# KEY.net
KiCad netlist of a schematic drawn in Altium Designer
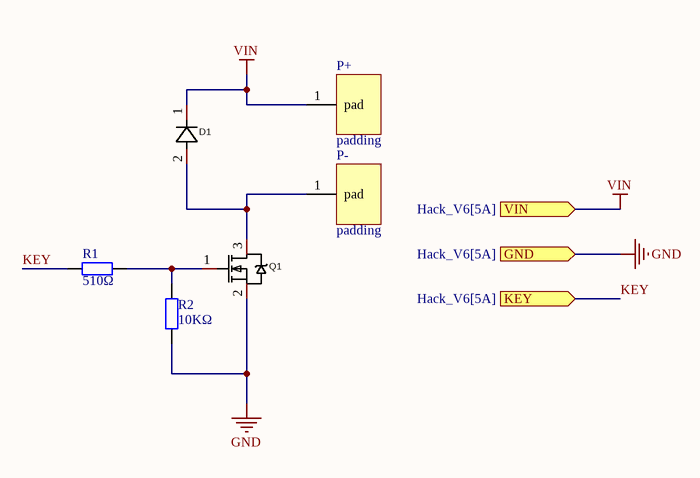
[diagram p0: KEY.SchDoc]

(export (version "E")
  (design (tool "Eeschema 10.0.6"))
  (components
    (comp (ref "D1")
      (value "DSK16")
      (footprint "DSK16")
      (fields (field (name "MANUFACTURER") "HXY MOSFET(华轩阳电子)"))
      (libsource (lib "Hack_V4") (part "DSK16"))
    )
    (comp (ref "P+") (value "padding") (footprint "PADDING1") (libsource (lib "Hack_V4") (part "padding1")))
    (comp (ref "P-") (value "padding") (footprint "PADDING1") (libsource (lib "Hack_V4") (part "padding1")))
    (comp (ref "Q1")
      (value "AO3442")
      (footprint "AO3442")
      (fields (field (name "MANUFACTURER") "AOS"))
      (libsource (lib "Hack_V3") (part "AO3442"))
    )
    (comp (ref "R1")
      (value "510Ω")
      (footprint "0603_R")
      (description "resistance")
      (libsource (lib "Hack_V6") (part "RES"))
    )
    (comp (ref "R2")
      (value "10KΩ")
      (footprint "0603_R")
      (description "resistance")
      (libsource (lib "") (part "RES_1"))
    )
  )
  (nets
    (net (code "1") (name "/KEY") (class "Default")
      (node (ref "R1") (pin "1") (pinfunction "1_1") (pintype "passive"))
    )
    (net (code "2") (name "GND") (class "Default")
      (node (ref "Q1") (pin "2") (pinfunction "S_2") (pintype "passive"))
      (node (ref "R2") (pin "1") (pinfunction "1_1") (pintype "passive"))
    )
    (net (code "3") (name "Net-(D1-A)") (class "Default")
      (node (ref "D1") (pin "2") (pinfunction "A_2") (pintype "passive"))
      (node (ref "P-") (pin "1") (pinfunction "pad_1") (pintype "passive"))
      (node (ref "Q1") (pin "3") (pinfunction "D_3") (pintype "passive"))
    )
    (net (code "4") (name "Net-(Q1-G)") (class "Default")
      (node (ref "Q1") (pin "1") (pinfunction "G_1") (pintype "passive"))
      (node (ref "R1") (pin "2") (pinfunction "2_2") (pintype "passive"))
      (node (ref "R2") (pin "2") (pinfunction "2_2") (pintype "passive"))
    )
    (net (code "5") (name "VIN") (class "Default")
      (node (ref "D1") (pin "1") (pinfunction "K_1") (pintype "passive"))
      (node (ref "P+") (pin "1") (pinfunction "pad_1") (pintype "passive"))
    )
  )
)
